# SAOA.net
KiCad netlist of a schematic drawn in EAGLE
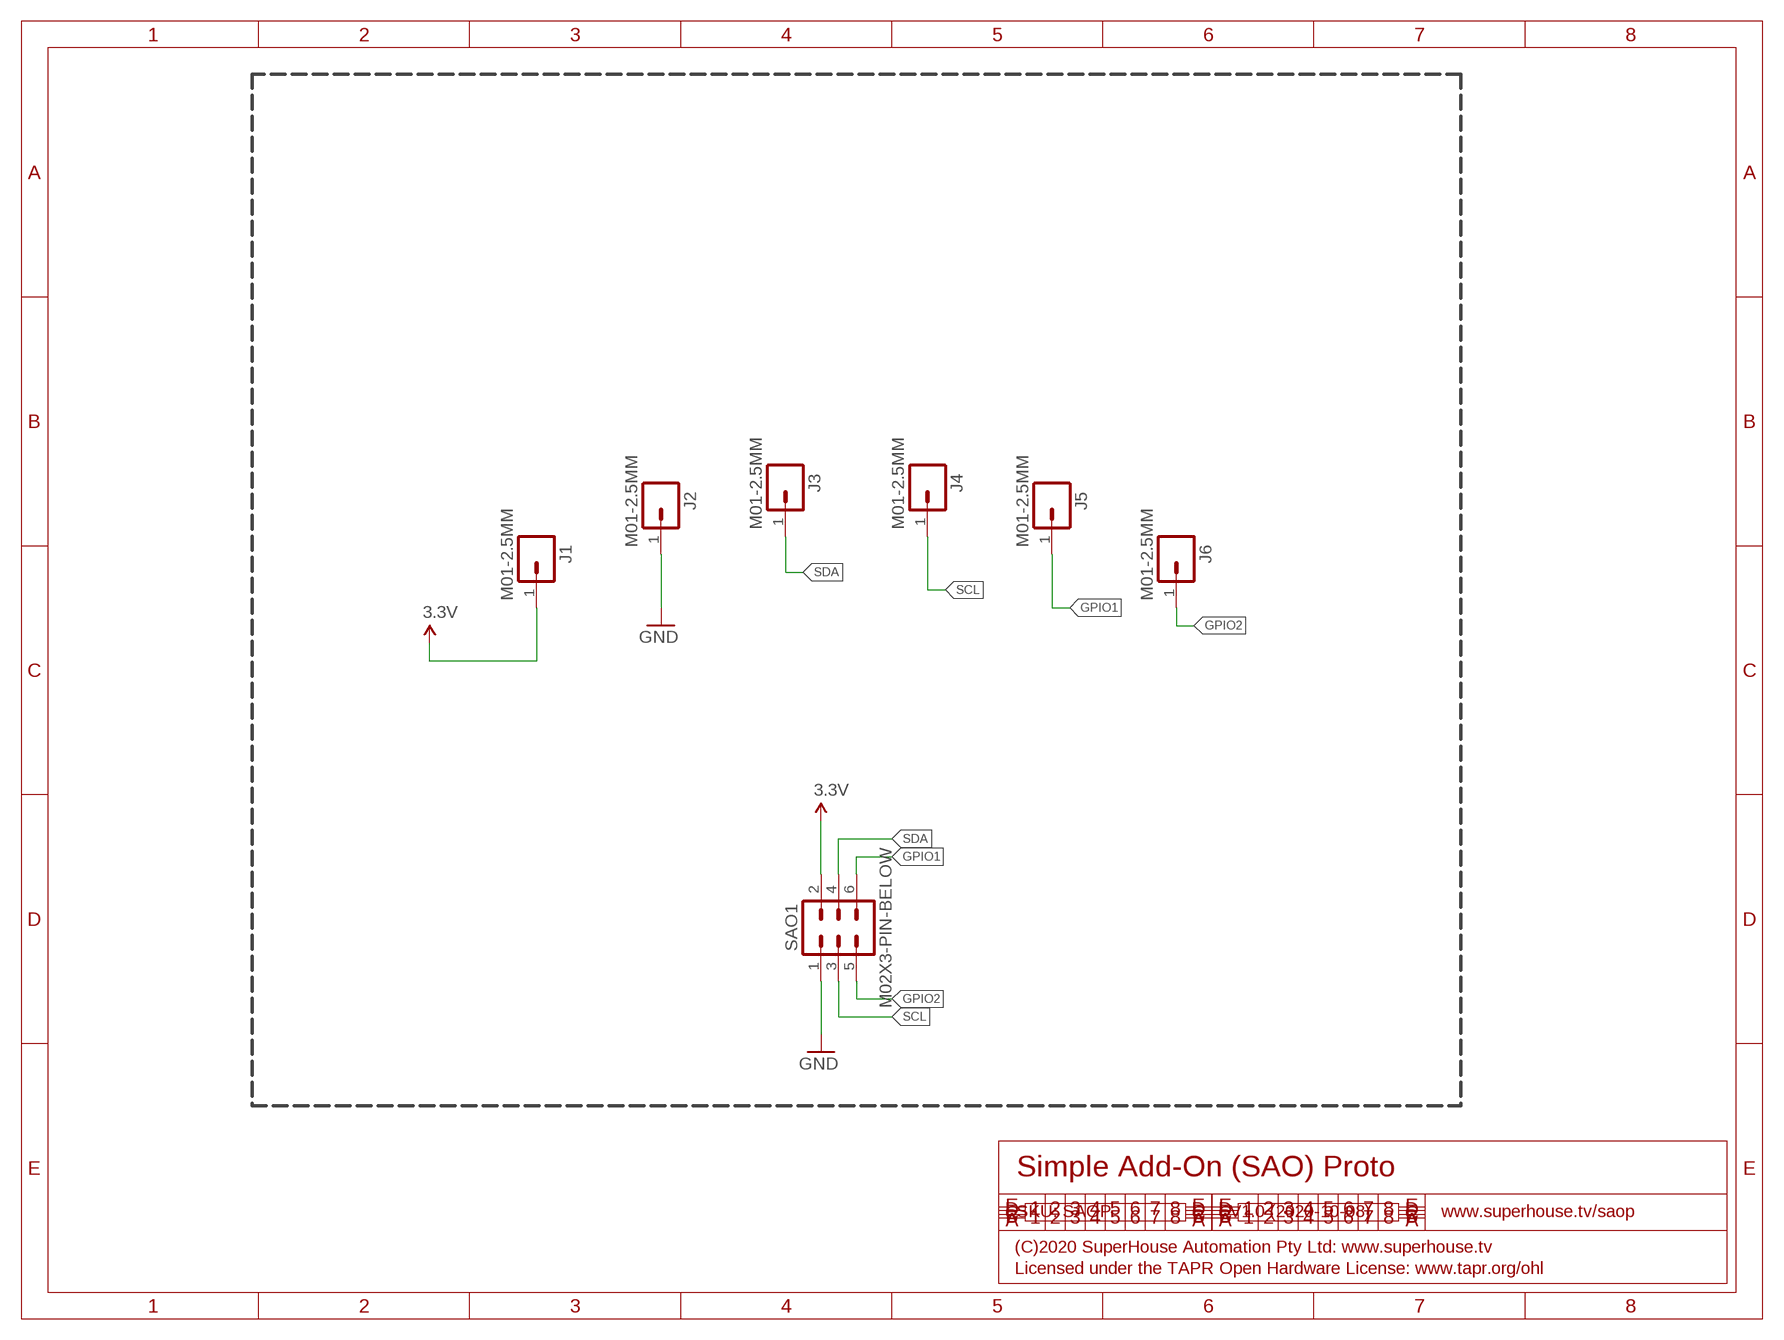
[diagram p0: schematic, sheet 1]

(export (version "E")
  (design (tool "Eeschema 10.0.6"))
  (components
    (comp (ref "J1")
      (value "M01-2.5MM")
      (footprint "eagle-import:1X01-2.5MM")
      (libsource (lib "eagle-import") (part "M01-2.5MM"))
    )
    (comp (ref "J2")
      (value "M01-2.5MM")
      (footprint "eagle-import:1X01-2.5MM")
      (libsource (lib "eagle-import") (part "M01-2.5MM"))
    )
    (comp (ref "J3")
      (value "M01-2.5MM")
      (footprint "eagle-import:1X01-2.5MM")
      (libsource (lib "eagle-import") (part "M01-2.5MM"))
    )
    (comp (ref "J4")
      (value "M01-2.5MM")
      (footprint "eagle-import:1X01-2.5MM")
      (libsource (lib "eagle-import") (part "M01-2.5MM"))
    )
    (comp (ref "J5")
      (value "M01-2.5MM")
      (footprint "eagle-import:1X01-2.5MM")
      (libsource (lib "eagle-import") (part "M01-2.5MM"))
    )
    (comp (ref "J6")
      (value "M01-2.5MM")
      (footprint "eagle-import:1X01-2.5MM")
      (libsource (lib "eagle-import") (part "M01-2.5MM"))
    )
    (comp (ref "SAO1")
      (value "M02X3-PIN-BELOW")
      (footprint "eagle-import:2X03-P-BELOW")
      (libsource (lib "eagle-import") (part "M02X3-PIN-BELOW"))
    )
  )
  (nets
    (net (code "1") (name "3.3V") (class "Default")
      (node (ref "J1") (pin "1") (pinfunction "1_1") (pintype "passive"))
      (node (ref "SAO1") (pin "2") (pinfunction "2_2") (pintype "passive"))
    )
    (net (code "2") (name "GND") (class "Default")
      (node (ref "J2") (pin "1") (pinfunction "1_1") (pintype "passive"))
      (node (ref "SAO1") (pin "1") (pinfunction "1_1") (pintype "passive"))
    )
    (net (code "3") (name "GPIO1") (class "Default")
      (node (ref "J5") (pin "1") (pinfunction "1_1") (pintype "passive"))
      (node (ref "SAO1") (pin "6") (pinfunction "6_6") (pintype "passive"))
    )
    (net (code "4") (name "GPIO2") (class "Default")
      (node (ref "J6") (pin "1") (pinfunction "1_1") (pintype "passive"))
      (node (ref "SAO1") (pin "5") (pinfunction "5_5") (pintype "passive"))
    )
    (net (code "5") (name "SCL") (class "Default")
      (node (ref "J4") (pin "1") (pinfunction "1_1") (pintype "passive"))
      (node (ref "SAO1") (pin "3") (pinfunction "3_3") (pintype "passive"))
    )
    (net (code "6") (name "SDA") (class "Default")
      (node (ref "J3") (pin "1") (pinfunction "1_1") (pintype "passive"))
      (node (ref "SAO1") (pin "4") (pinfunction "4_4") (pintype "passive"))
    )
  )
)
